# Gyroscope.net
KiCad netlist of a schematic drawn in Altium Designer
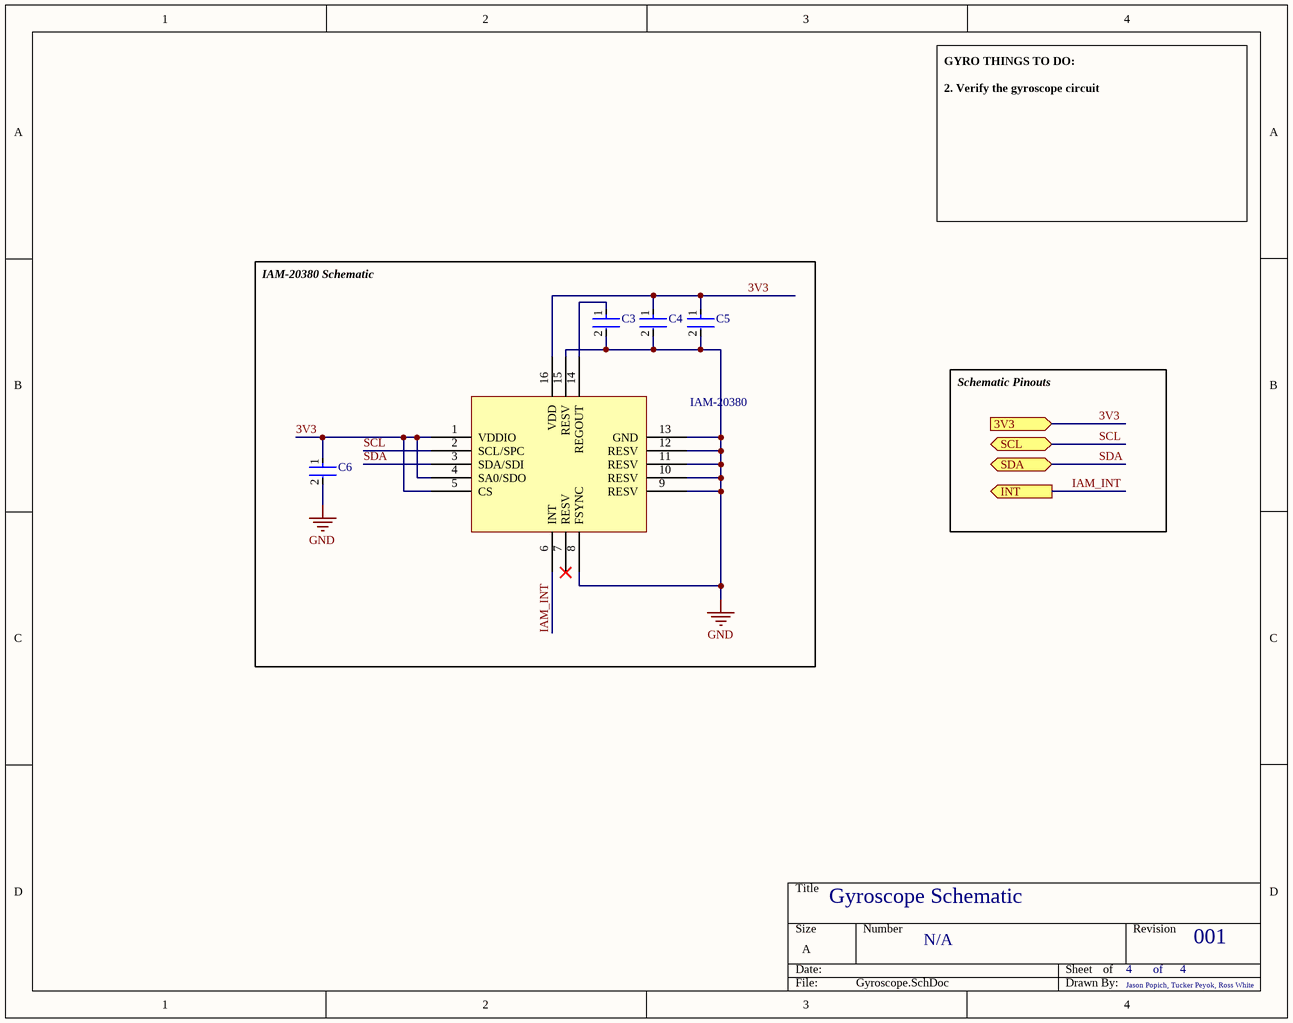
[diagram p0: Gyroscope.SchDoc]

(export (version "E")
  (design (tool "Eeschema 10.0.6"))
  (components
    (comp (ref "*")
      (value "IAM-20380")
      (footprint "Gyro - IAM20380")
      (description "IAM-20380 High Performance Gyroscope")
      (libsource (lib "GAINS_SCH") (part "IAM-20380"))
    )
    (comp (ref "C3")
      (value "GJ821BR71H105KA12L")
      (footprint "FP-GJ821B-0_1-MFG")
      (description "CAP CER 1UF 50V X7R 0805")
      (fields (field (name "TOLERANCE") "10%"))
      (libsource (lib "Altium Content Vault") (part "02cd4be3c70576c341d710602a673aa"))
    )
    (comp (ref "C4")
      (value "GJ821BR71H105KA12L")
      (footprint "FP-GJ821B-0_1-MFG")
      (description "CAP CER 1UF 50V X7R 0805")
      (fields (field (name "TOLERANCE") "10%"))
      (libsource (lib "Altium Content Vault") (part "02cd4be3c70576c341d710602a673aa"))
    )
    (comp (ref "C5")
      (value "GJ821BR71H105KA12L")
      (footprint "FP-GJ821B-0_1-MFG")
      (description "CAP CER 1UF 50V X7R 0805")
      (fields (field (name "TOLERANCE") "10%"))
      (libsource (lib "Altium Content Vault") (part "02cd4be3c70576c341d710602a673aa"))
    )
    (comp (ref "C6")
      (value "GCJ21BR72E103KXJ3L")
      (footprint "FP-GCJ21B-0_2-MFG")
      (description "CAP CER 10000PF 250V X7R 0805")
      (fields (field (name "TOLERANCE") "10%"))
      (libsource (lib "Altium Content Vault") (part "02cd4be3c70576c341d710602a673aa"))
    )
  )
  (nets
    (net (code "1") (name "/3V3") (class "Default")
      (node (ref "*") (pin "1") (pinfunction "VDDIO_1") (pintype "passive"))
      (node (ref "*") (pin "16") (pinfunction "VDD_16") (pintype "passive"))
      (node (ref "*") (pin "4") (pinfunction "SA0/SDO_4") (pintype "passive"))
      (node (ref "*") (pin "5") (pinfunction "CS_5") (pintype "passive"))
      (node (ref "C4") (pin "1") (pinfunction "1_1") (pintype "passive"))
      (node (ref "C5") (pin "1") (pinfunction "1_1") (pintype "passive"))
      (node (ref "C6") (pin "1") (pinfunction "1_1") (pintype "passive"))
    )
    (net (code "2") (name "/IAM_INT") (class "Default")
      (node (ref "*") (pin "6") (pinfunction "INT_6") (pintype "passive"))
    )
    (net (code "3") (name "/SCL") (class "Default")
      (node (ref "*") (pin "2") (pinfunction "SCL/SPC_2") (pintype "passive"))
    )
    (net (code "4") (name "/SDA") (class "Default")
      (node (ref "*") (pin "3") (pinfunction "SDA/SDI_3") (pintype "passive"))
    )
    (net (code "5") (name "GND") (class "Default")
      (node (ref "*") (pin "10") (pinfunction "RESV_10") (pintype "passive"))
      (node (ref "*") (pin "11") (pinfunction "RESV_11") (pintype "passive"))
      (node (ref "*") (pin "12") (pinfunction "RESV_12") (pintype "passive"))
      (node (ref "*") (pin "13") (pinfunction "GND_13") (pintype "passive"))
      (node (ref "*") (pin "15") (pinfunction "RESV_15") (pintype "passive"))
      (node (ref "*") (pin "8") (pinfunction "FSYNC_8") (pintype "passive"))
      (node (ref "*") (pin "9") (pinfunction "RESV_9") (pintype "passive"))
      (node (ref "C3") (pin "2") (pinfunction "2_2") (pintype "passive"))
      (node (ref "C4") (pin "2") (pinfunction "2_2") (pintype "passive"))
      (node (ref "C5") (pin "2") (pinfunction "2_2") (pintype "passive"))
      (node (ref "C6") (pin "2") (pinfunction "2_2") (pintype "passive"))
    )
    (net (code "6") (name "Net-(*-REGOUT)") (class "Default")
      (node (ref "*") (pin "14") (pinfunction "REGOUT_14") (pintype "passive"))
      (node (ref "C3") (pin "1") (pinfunction "1_1") (pintype "passive"))
    )
    (net (code "7") (name "unconnected-(*-RESV-Pad7)") (class "Default")
      (node (ref "*") (pin "7") (pinfunction "RESV_7") (pintype "passive+no_connect"))
    )
  )
)
